# brain_badge.net
KiCad netlist of a schematic drawn in EAGLE
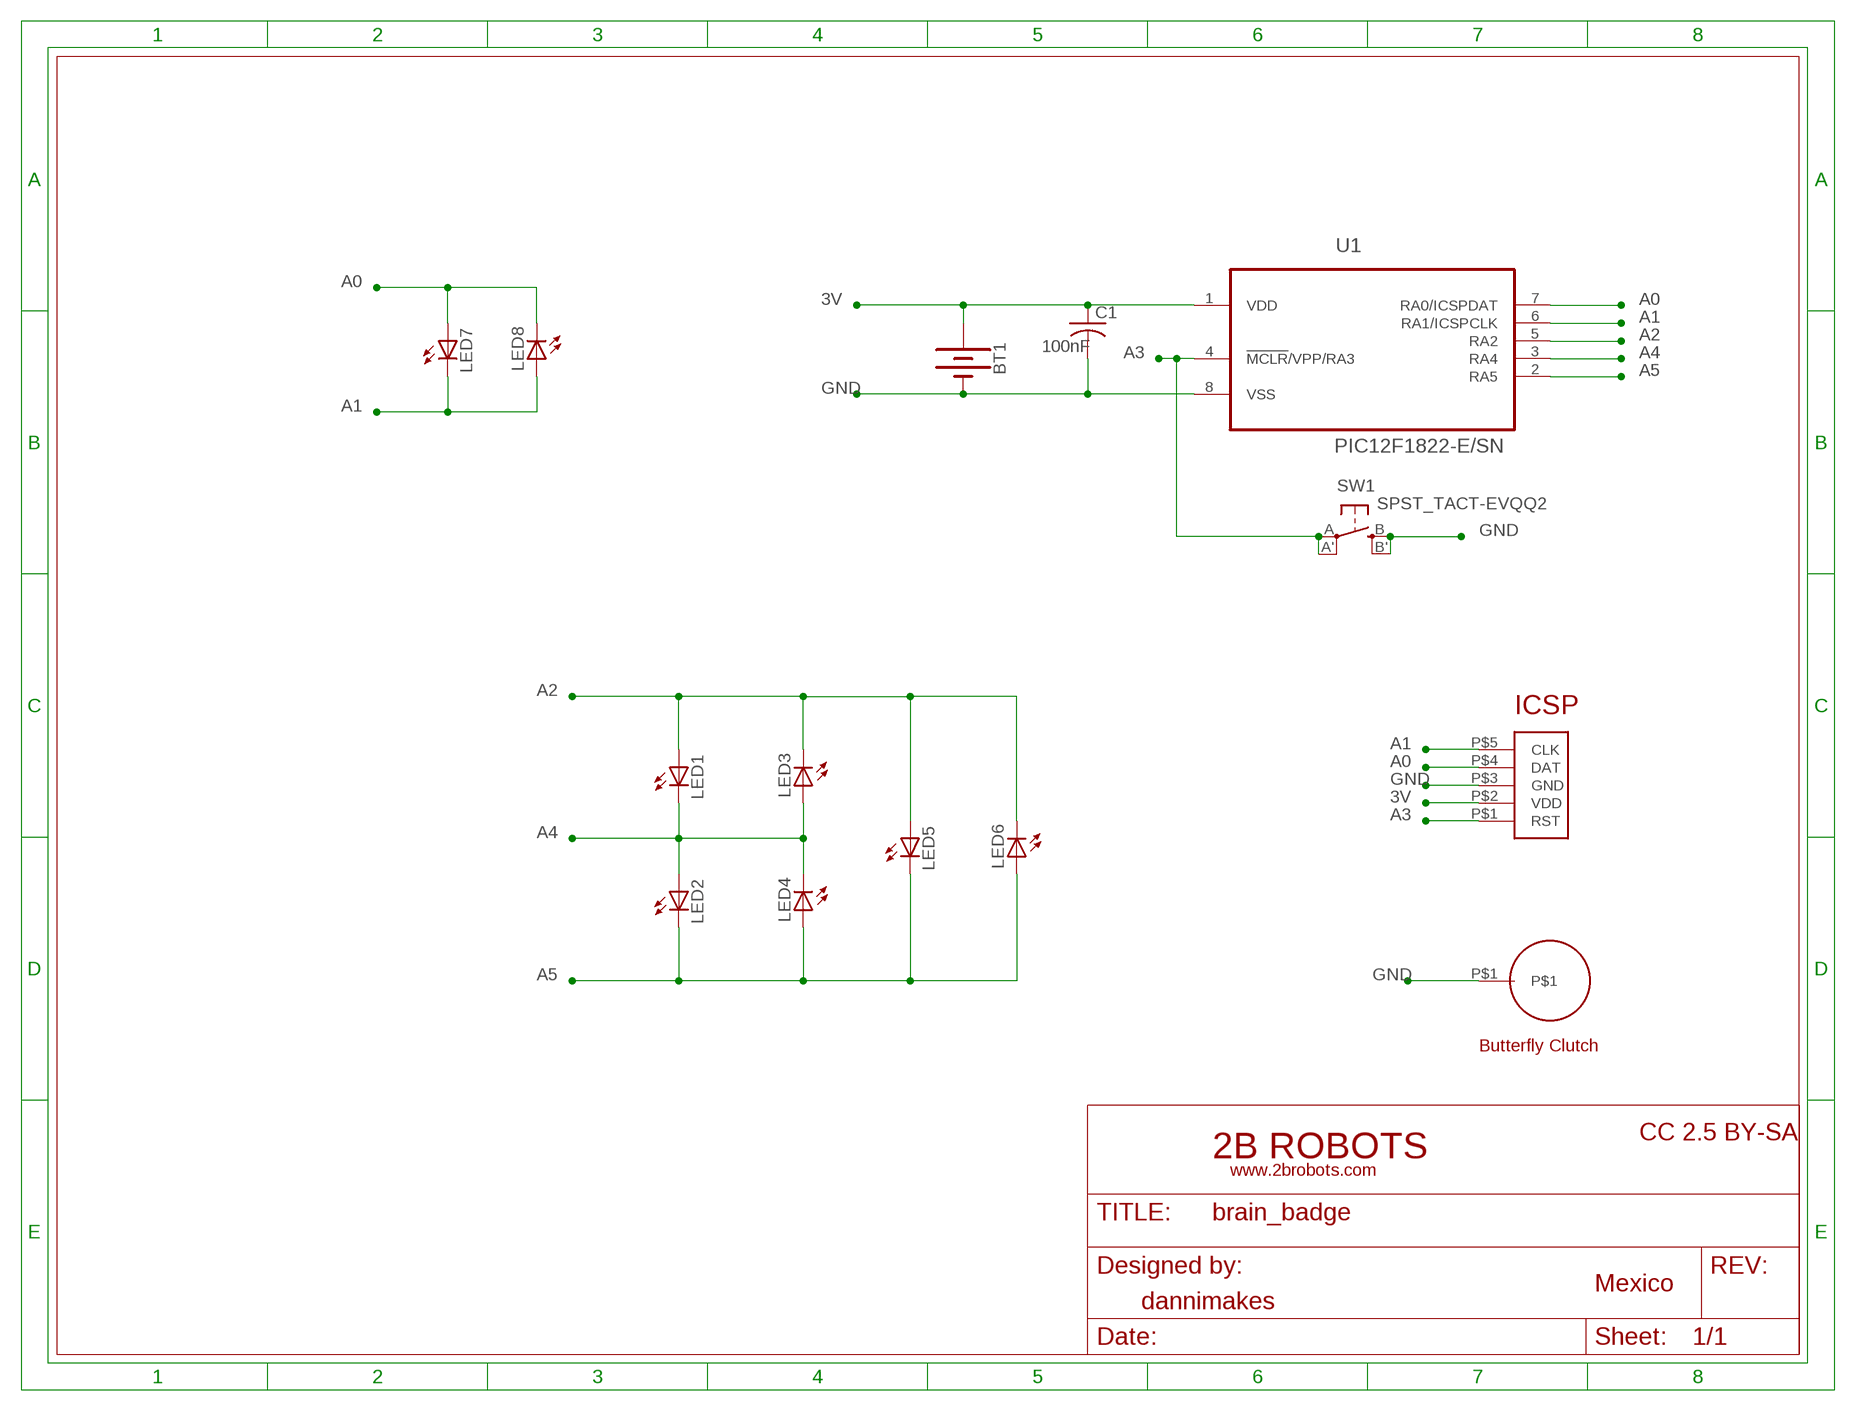
[diagram p0: schematic, sheet 1]

(export (version "E")
  (design (tool "Eeschema 10.0.6"))
  (components
    (comp (ref "BT1")
      (value "BATTERY-20MM_SMD")
      (footprint "eagle-import:BATTCON_20MM")
      (libsource (lib "eagle-import") (part "BATTERY-20MM_SMD"))
    )
    (comp (ref "C1")
      (value "100nF")
      (footprint "eagle-import:C0603K")
      (libsource (lib "eagle-import") (part "C-USC0603K"))
    )
    (comp (ref "LED1")
      (value "LEDCHIP-LED0603")
      (footprint "eagle-import:CHIP-LED0603")
      (libsource (lib "eagle-import") (part "LEDCHIP-LED0603"))
    )
    (comp (ref "LED2")
      (value "LEDCHIP-LED0603")
      (footprint "eagle-import:CHIP-LED0603")
      (libsource (lib "eagle-import") (part "LEDCHIP-LED0603"))
    )
    (comp (ref "LED3")
      (value "LEDCHIP-LED0603")
      (footprint "eagle-import:CHIP-LED0603")
      (libsource (lib "eagle-import") (part "LEDCHIP-LED0603"))
    )
    (comp (ref "LED4")
      (value "LEDCHIP-LED0603")
      (footprint "eagle-import:CHIP-LED0603")
      (libsource (lib "eagle-import") (part "LEDCHIP-LED0603"))
    )
    (comp (ref "LED5")
      (value "LEDCHIP-LED0603")
      (footprint "eagle-import:CHIP-LED0603")
      (libsource (lib "eagle-import") (part "LEDCHIP-LED0603"))
    )
    (comp (ref "LED6")
      (value "LEDCHIP-LED0603")
      (footprint "eagle-import:CHIP-LED0603")
      (libsource (lib "eagle-import") (part "LEDCHIP-LED0603"))
    )
    (comp (ref "LED7")
      (value "LEDCHIP-LED0603")
      (footprint "eagle-import:CHIP-LED0603")
      (libsource (lib "eagle-import") (part "LEDCHIP-LED0603"))
    )
    (comp (ref "LED8")
      (value "LEDCHIP-LED0603")
      (footprint "eagle-import:CHIP-LED0603")
      (libsource (lib "eagle-import") (part "LEDCHIP-LED0603"))
    )
    (comp (ref "SW1")
      (value "SPST_TACT-EVQQ2")
      (footprint "eagle-import:EVQ-Q2")
      (libsource (lib "eagle-import") (part "SPST_TACT-EVQQ2"))
    )
    (comp (ref "U$1")
      (value "ICSP_POGO")
      (footprint "eagle-import:ICSP_POGO")
      (libsource (lib "eagle-import") (part "ICSP_POGO"))
    )
    (comp (ref "U$2")
      (value "BUTTERFLY_CLUTCH")
      (footprint "eagle-import:BUTTERFLY_CLUTCH")
      (libsource (lib "eagle-import") (part "BUTTERFLY_CLUTCH"))
    )
    (comp (ref "U1")
      (value "PIC12F1822-E/SN")
      (footprint "eagle-import:SOIC127P600X175-8N")
      (libsource (lib "eagle-import") (part "PIC12F1822-E/SN"))
    )
  )
  (nets
    (net (code "1") (name "/3V") (class "Default")
      (node (ref "BT1") (pin "1") (pinfunction "+_1") (pintype "power_in"))
      (node (ref "BT1") (pin "3") (pinfunction "+_3") (pintype "power_in"))
      (node (ref "C1") (pin "1") (pinfunction "1_1") (pintype "passive"))
      (node (ref "U$1") (pin "P$2") (pinfunction "VDD_P$2") (pintype "bidirectional"))
      (node (ref "U1") (pin "1") (pinfunction "VDD_1") (pintype "power_in"))
    )
    (net (code "2") (name "/A0") (class "Default")
      (node (ref "LED7") (pin "A") (pinfunction "A_A") (pintype "passive"))
      (node (ref "LED8") (pin "C") (pinfunction "C_C") (pintype "passive"))
      (node (ref "U$1") (pin "P$4") (pinfunction "DAT_P$4") (pintype "bidirectional"))
      (node (ref "U1") (pin "7") (pinfunction "RA0/ICSPDAT_7") (pintype "bidirectional"))
    )
    (net (code "3") (name "/A1") (class "Default")
      (node (ref "LED7") (pin "C") (pinfunction "C_C") (pintype "passive"))
      (node (ref "LED8") (pin "A") (pinfunction "A_A") (pintype "passive"))
      (node (ref "U$1") (pin "P$5") (pinfunction "CLK_P$5") (pintype "bidirectional"))
      (node (ref "U1") (pin "6") (pinfunction "RA1/ICSPCLK_6") (pintype "bidirectional"))
    )
    (net (code "4") (name "/A2") (class "Default")
      (node (ref "LED1") (pin "A") (pinfunction "A_A") (pintype "passive"))
      (node (ref "LED3") (pin "C") (pinfunction "C_C") (pintype "passive"))
      (node (ref "LED5") (pin "A") (pinfunction "A_A") (pintype "passive"))
      (node (ref "LED6") (pin "C") (pinfunction "C_C") (pintype "passive"))
      (node (ref "U1") (pin "5") (pinfunction "RA2_5") (pintype "bidirectional"))
    )
    (net (code "5") (name "/A3") (class "Default")
      (node (ref "SW1") (pin "A") (pinfunction "P_A") (pintype "passive"))
      (node (ref "SW1") (pin "A'") (pinfunction "P1_A'") (pintype "passive"))
      (node (ref "U$1") (pin "P$1") (pinfunction "RST_P$1") (pintype "bidirectional"))
      (node (ref "U1") (pin "4") (pinfunction "~{MCLR}/VPP/RA3_4") (pintype "input"))
    )
    (net (code "6") (name "/A4") (class "Default")
      (node (ref "LED1") (pin "C") (pinfunction "C_C") (pintype "passive"))
      (node (ref "LED2") (pin "A") (pinfunction "A_A") (pintype "passive"))
      (node (ref "LED3") (pin "A") (pinfunction "A_A") (pintype "passive"))
      (node (ref "LED4") (pin "C") (pinfunction "C_C") (pintype "passive"))
      (node (ref "U1") (pin "3") (pinfunction "RA4_3") (pintype "bidirectional"))
    )
    (net (code "7") (name "/A5") (class "Default")
      (node (ref "LED2") (pin "C") (pinfunction "C_C") (pintype "passive"))
      (node (ref "LED4") (pin "A") (pinfunction "A_A") (pintype "passive"))
      (node (ref "LED5") (pin "C") (pinfunction "C_C") (pintype "passive"))
      (node (ref "LED6") (pin "A") (pinfunction "A_A") (pintype "passive"))
      (node (ref "U1") (pin "2") (pinfunction "RA5_2") (pintype "bidirectional"))
    )
    (net (code "8") (name "/GND") (class "Default")
      (node (ref "BT1") (pin "2") (pinfunction "-_2") (pintype "power_in"))
      (node (ref "C1") (pin "2") (pinfunction "2_2") (pintype "passive"))
      (node (ref "SW1") (pin "B") (pinfunction "S_B") (pintype "passive"))
      (node (ref "SW1") (pin "B'") (pinfunction "S1_B'") (pintype "passive"))
      (node (ref "U$1") (pin "P$3") (pinfunction "GND_P$3") (pintype "bidirectional"))
      (node (ref "U$2") (pin "P$1") (pinfunction "P$1_P$1") (pintype "bidirectional"))
      (node (ref "U1") (pin "8") (pinfunction "VSS_8") (pintype "power_in"))
    )
  )
)
